# SEG_pressure_gauge_up_V2_1.net
KiCad netlist of a schematic drawn in Altium Designer
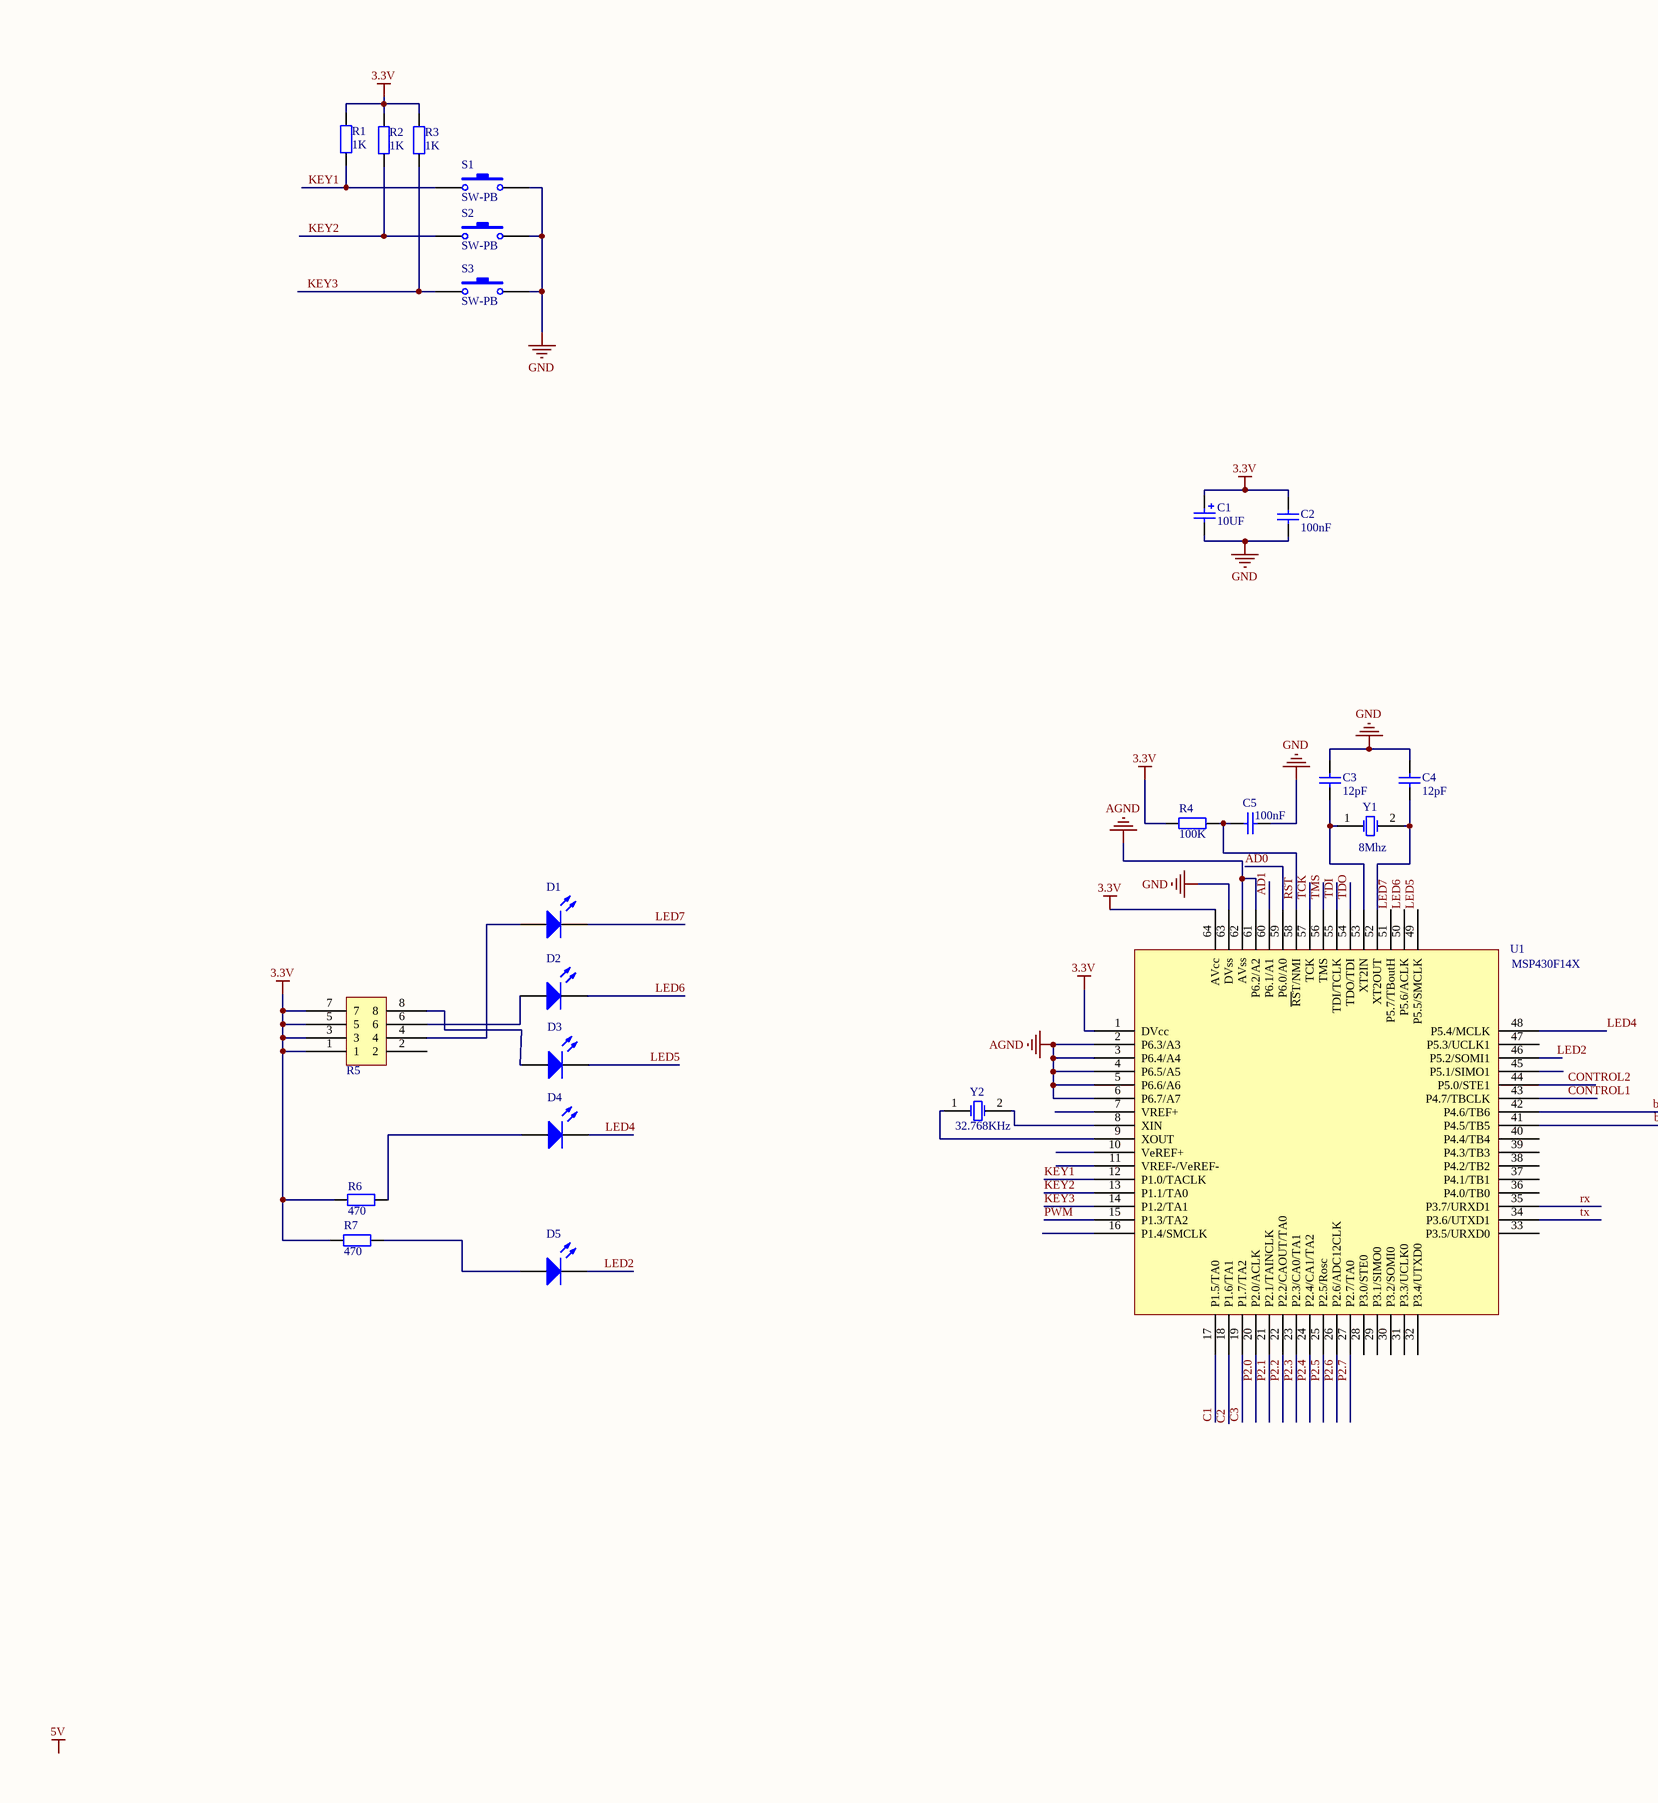
[diagram p0: SEG_pressure gauge_up  V2.1.SchDoc, left]
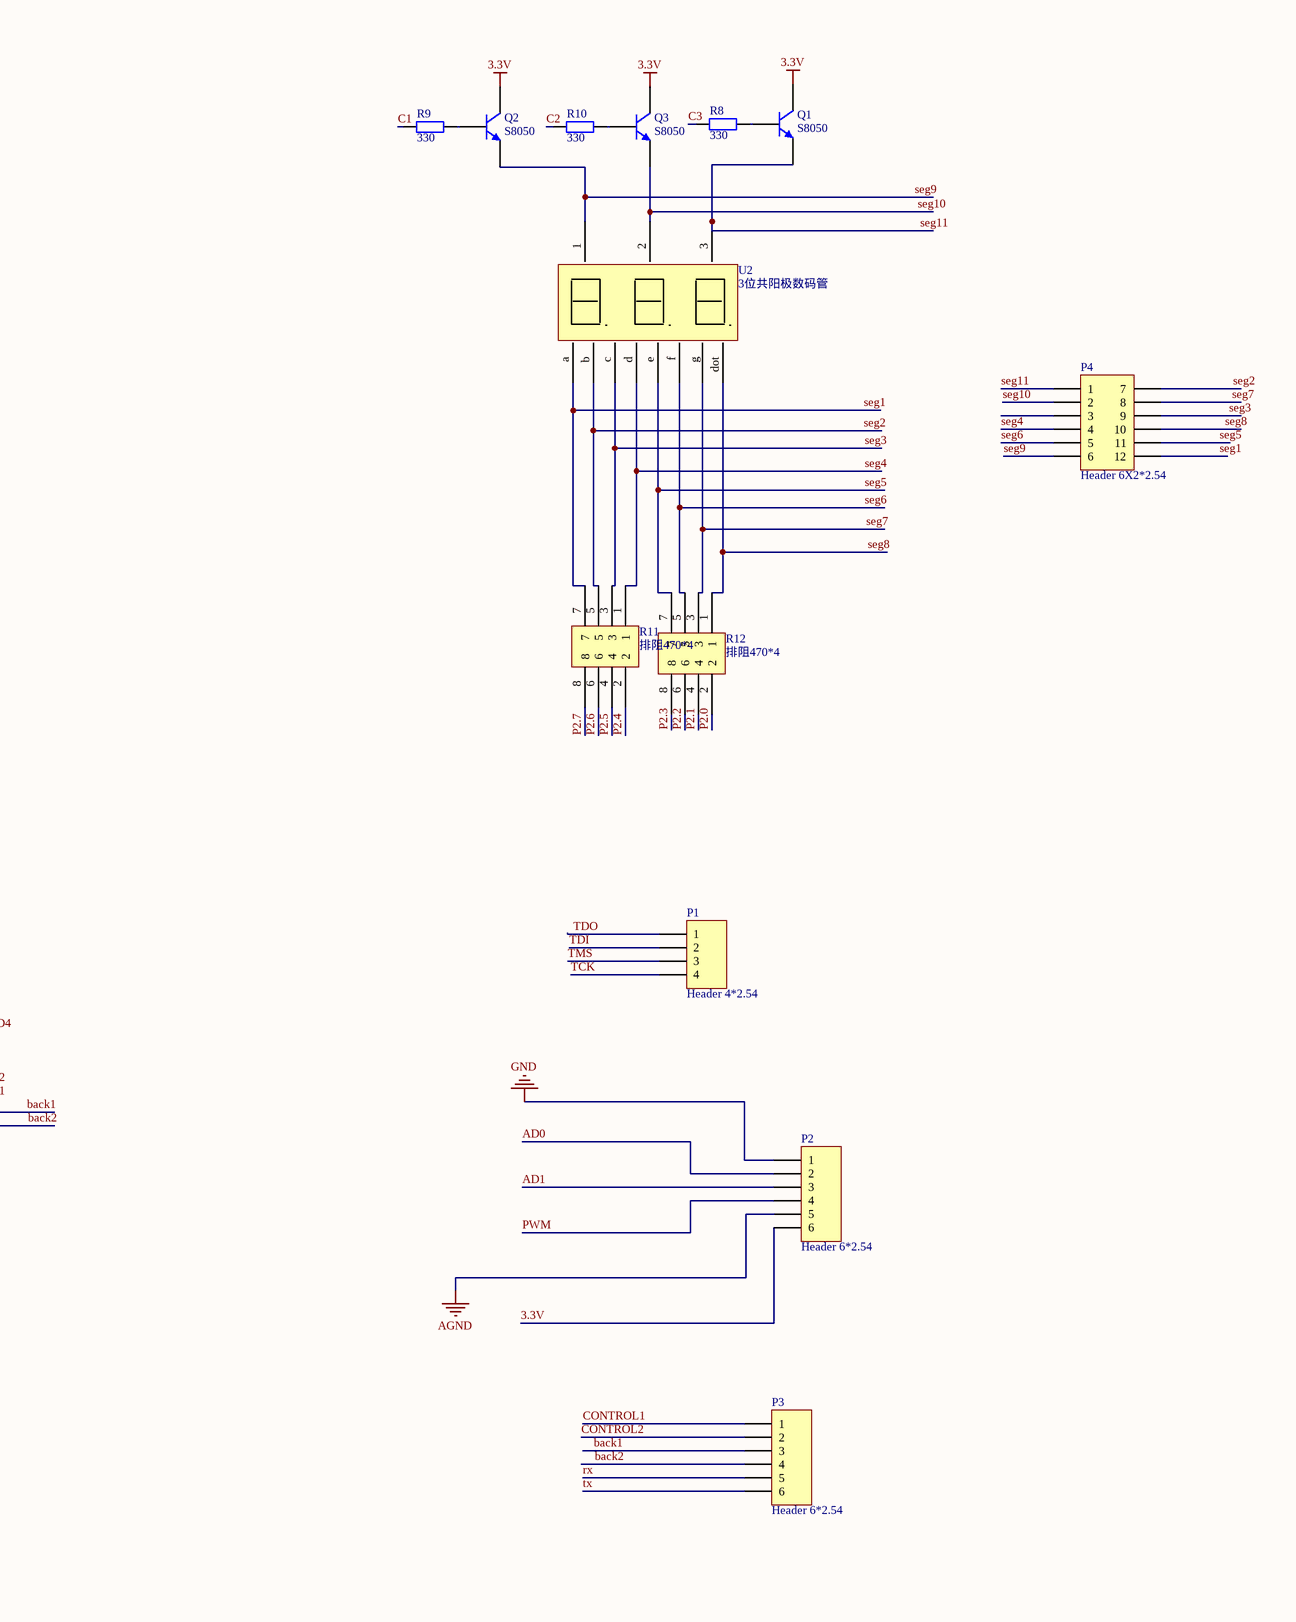
[diagram p1: SEG_pressure gauge_up  V2.1.SchDoc, right]

(export (version "E")
  (design (tool "Eeschema 10.0.6"))
  (components
    (comp (ref "C1")
      (value "10UF")
      (footprint "3216")
      (description "Polarized Capacitor (Axial)")
      (fields (field (name "Comment") "10uf") (field (name "PUBLISHER") "Altium Limited"))
      (libsource (lib "Miscellaneous Devices") (part "Cap Pol2"))
    )
    (comp (ref "C2")
      (value "100nF")
      (footprint "0805_C_Y")
      (description "Capacitor")
      (fields (field (name "Comment") "100nf") (field (name "PUBLISHER") "Altium Limited"))
      (libsource (lib "Miscellaneous Devices") (part "Cap"))
    )
    (comp (ref "C3")
      (value "12pF")
      (footprint "0805_C_Y")
      (description "Capacitor")
      (fields (field (name "Comment") "12pf") (field (name "PUBLISHER") "Altium Limited"))
      (libsource (lib "Miscellaneous Devices") (part "Cap"))
    )
    (comp (ref "C4")
      (value "12pF")
      (footprint "0805_C_Y")
      (description "Capacitor")
      (fields (field (name "Comment") "12pf") (field (name "PUBLISHER") "Altium Limited"))
      (libsource (lib "Miscellaneous Devices") (part "Cap"))
    )
    (comp (ref "C5")
      (value "100nF")
      (footprint "0805_C_Y")
      (description "Capacitor")
      (fields (field (name "Comment") "100nf") (field (name "PUBLISHER") "Altium Limited"))
      (libsource (lib "Miscellaneous Devices") (part "Cap"))
    )
    (comp (ref "D1")
      (value "LED")
      (footprint "LED")
      (description "Typical INFRARED GaAs LED")
      (fields (field (name "PUBLISHER") "Altium Limited"))
      (libsource (lib "Miscellaneous Devices") (part "LED0"))
    )
    (comp (ref "D2")
      (value "LED")
      (footprint "LED")
      (description "Typical INFRARED GaAs LED")
      (fields (field (name "PUBLISHER") "Altium Limited"))
      (libsource (lib "Miscellaneous Devices") (part "LED0"))
    )
    (comp (ref "D3")
      (value "LED")
      (footprint "LED")
      (description "Typical INFRARED GaAs LED")
      (fields (field (name "PUBLISHER") "Altium Limited"))
      (libsource (lib "Miscellaneous Devices") (part "LED0"))
    )
    (comp (ref "D4")
      (value "LED")
      (footprint "LED")
      (description "Typical INFRARED GaAs LED")
      (fields (field (name "PUBLISHER") "Altium Limited"))
      (libsource (lib "Miscellaneous Devices") (part "LED0"))
    )
    (comp (ref "D5")
      (value "LED")
      (footprint "LED")
      (description "Typical INFRARED GaAs LED")
      (fields (field (name "PUBLISHER") "Altium Limited"))
      (libsource (lib "Miscellaneous Devices") (part "LED0"))
    )
    (comp (ref "P1")
      (value "Header 4*2.54")
      (footprint "HDR1X4")
      (description "Header, 4-Pin")
      (fields (field (name "PUBLISHER") "Altium Limited"))
      (libsource (lib "Miscellaneous Connectors") (part "Header 4"))
    )
    (comp (ref "P2")
      (value "Header 6*2.54")
      (footprint "SEG_pressure gauge_up  V2.1:HDR1X6")
      (description "Header, 6-Pin")
      (fields (field (name "PUBLISHER") "Altium Limited"))
      (libsource (lib "Miscellaneous Connectors") (part "Header 6"))
    )
    (comp (ref "P3")
      (value "Header 6*2.54")
      (footprint "SEG_pressure gauge_up  V2.1:HDR1X6")
      (description "Header, 6-Pin")
      (fields (field (name "PUBLISHER") "Altium Limited"))
      (libsource (lib "Miscellaneous Connectors") (part "Header 6"))
    )
    (comp (ref "P4")
      (value "Header 6X2*2.54")
      (footprint "HDR2X6_CEN")
      (description "Header, 6-Pin, Dual row")
      (fields (field (name "PUBLISHER") "Altium Limited"))
      (libsource (lib "Miscellaneous Connectors") (part "Header 6X2A"))
    )
    (comp (ref "Q1")
      (value "S8050")
      (footprint "SOT-23_Y")
      (description "NPN General Purpose Amplifier")
      (fields (field (name "PUBLISHER") "Altium Limited"))
      (libsource (lib "Miscellaneous Devices") (part "2N3904"))
    )
    (comp (ref "Q2")
      (value "S8050")
      (footprint "SOT-23_Y")
      (description "NPN General Purpose Amplifier")
      (fields (field (name "PUBLISHER") "Altium Limited"))
      (libsource (lib "Miscellaneous Devices") (part "2N3904"))
    )
    (comp (ref "Q3")
      (value "S8050")
      (footprint "SOT-23_Y")
      (description "NPN General Purpose Amplifier")
      (fields (field (name "PUBLISHER") "Altium Limited"))
      (libsource (lib "Miscellaneous Devices") (part "2N3904"))
    )
    (comp (ref "R1")
      (value "1K")
      (footprint "0805_R_Y")
      (description "Resistor")
      (fields (field (name "Comment") "1k") (field (name "PUBLISHER") "Altium Limited"))
      (libsource (lib "") (part "Res2_1"))
    )
    (comp (ref "R2")
      (value "1K")
      (footprint "0805_R_Y")
      (description "Resistor")
      (fields (field (name "Comment") "1k") (field (name "PUBLISHER") "Altium Limited"))
      (libsource (lib "") (part "Res2_1"))
    )
    (comp (ref "R3")
      (value "1K")
      (footprint "0805_R_Y")
      (description "Resistor")
      (fields (field (name "Comment") "1k") (field (name "PUBLISHER") "Altium Limited"))
      (libsource (lib "") (part "Res2_1"))
    )
    (comp (ref "R4")
      (value "100K")
      (footprint "0805_R_Y")
      (description "Resistor")
      (fields (field (name "Comment") "100k") (field (name "PUBLISHER") "Altium Limited"))
      (libsource (lib "Miscellaneous Devices") (part "Res2"))
    )
    (comp (ref "R5") (value "排阻470*4") (footprint "8P4R_0603") (libsource (lib "biao2") (part "排阻 8P4R")))
    (comp (ref "R6")
      (value "470")
      (footprint "0805_R_Y")
      (description "Resistor")
      (fields (field (name "PUBLISHER") "Altium Limited"))
      (libsource (lib "Miscellaneous Devices") (part "Res2"))
    )
    (comp (ref "R7")
      (value "470")
      (footprint "0805_R_Y")
      (description "Resistor")
      (fields (field (name "PUBLISHER") "Altium Limited"))
      (libsource (lib "Miscellaneous Devices") (part "Res2"))
    )
    (comp (ref "R8")
      (value "330")
      (footprint "0805_R_Y")
      (description "Resistor")
      (fields (field (name "PUBLISHER") "Altium Limited"))
      (libsource (lib "") (part "Res2_2"))
    )
    (comp (ref "R9")
      (value "330")
      (footprint "0805_R_Y")
      (description "Resistor")
      (fields (field (name "PUBLISHER") "Altium Limited"))
      (libsource (lib "") (part "Res2_2"))
    )
    (comp (ref "R10")
      (value "330")
      (footprint "0805_R_Y")
      (description "Resistor")
      (fields (field (name "PUBLISHER") "Altium Limited"))
      (libsource (lib "") (part "Res2_2"))
    )
    (comp (ref "R11") (value "排阻470*4") (footprint "8P4R_0603") (libsource (lib "xianshi") (part "排阻 8P4R")))
    (comp (ref "R12") (value "排阻470*4") (footprint "8P4R_0603") (libsource (lib "xianshi") (part "排阻 8P4R")))
    (comp (ref "S1")
      (value "SW-PB")
      (footprint "SW-SMD1")
      (description "Switch")
      (fields (field (name "PUBLISHER") "Altium Limited"))
      (libsource (lib "Miscellaneous Devices") (part "SW-PB"))
    )
    (comp (ref "S2")
      (value "SW-PB")
      (footprint "SW-SMD1")
      (description "Switch")
      (fields (field (name "PUBLISHER") "Altium Limited"))
      (libsource (lib "Miscellaneous Devices") (part "SW-PB"))
    )
    (comp (ref "S3")
      (value "SW-PB")
      (footprint "SW-SMD1")
      (description "Switch")
      (fields (field (name "PUBLISHER") "Altium Limited"))
      (libsource (lib "Miscellaneous Devices") (part "SW-PB"))
    )
    (comp (ref "U1")
      (value "MSP430F14X")
      (footprint "S-PQFP-G64_Y")
      (libsource (lib "MSP430原理图") (part "MSP430F14X"))
    )
    (comp (ref "U2")
      (value "3位共阳极数码管")
      (footprint "xianshi:3位数码管0.56")
      (libsource (lib "kelei") (part "3位共阳极数码管"))
    )
    (comp (ref "Y1")
      (value "8Mhz")
      (footprint "HC-49/S_Y")
      (description "Crystal Oscillator")
      (fields (field (name "Comment") "晶振8M") (field (name "PUBLISHER") "Altium Limited"))
      (libsource (lib "Miscellaneous Devices") (part "XTAL"))
    )
    (comp (ref "Y2")
      (value "32.768KHz")
      (footprint "Crastal_32.768_Y")
      (description "Crystal Oscillator")
      (fields (field (name "Comment") "晶振32.768k") (field (name "PUBLISHER") "Altium Limited"))
      (libsource (lib "Miscellaneous Devices") (part "XTAL"))
    )
  )
  (nets
    (net (code "1") (name "/AD0") (class "Default")
      (node (ref "P2") (pin "2") (pinfunction "2_2") (pintype "passive"))
      (node (ref "U1") (pin "59") (pinfunction "P6.0/A0_59") (pintype "power_in"))
    )
    (net (code "2") (name "/AD1") (class "Default")
      (node (ref "P2") (pin "3") (pinfunction "3_3") (pintype "passive"))
      (node (ref "U1") (pin "60") (pinfunction "P6.1/A1_60") (pintype "power_in"))
    )
    (net (code "3") (name "/C1") (class "Default")
      (node (ref "R9") (pin "2") (pinfunction "2_2") (pintype "passive"))
      (node (ref "U1") (pin "17") (pinfunction "P1.5/TA0_17") (pintype "power_in"))
    )
    (net (code "4") (name "/C2") (class "Default")
      (node (ref "R10") (pin "2") (pinfunction "2_2") (pintype "passive"))
      (node (ref "U1") (pin "18") (pinfunction "P1.6/TA1_18") (pintype "power_in"))
    )
    (net (code "5") (name "/C3") (class "Default")
      (node (ref "R8") (pin "2") (pinfunction "2_2") (pintype "passive"))
      (node (ref "U1") (pin "19") (pinfunction "P1.7/TA2_19") (pintype "power_in"))
    )
    (net (code "6") (name "/CONTROL1") (class "Default")
      (node (ref "P3") (pin "1") (pinfunction "1_1") (pintype "passive"))
      (node (ref "U1") (pin "43") (pinfunction "P4.7/TBCLK_43") (pintype "power_in"))
    )
    (net (code "7") (name "/CONTROL2") (class "Default")
      (node (ref "P3") (pin "2") (pinfunction "2_2") (pintype "passive"))
      (node (ref "U1") (pin "44") (pinfunction "P5.0/STE1_44") (pintype "power_in"))
    )
    (net (code "8") (name "/KEY1") (class "Default")
      (node (ref "R1") (pin "1") (pinfunction "1_1") (pintype "passive"))
      (node (ref "S1") (pin "1") (pinfunction "1_1") (pintype "passive"))
      (node (ref "U1") (pin "12") (pinfunction "P1.0/TACLK_12") (pintype "power_in"))
    )
    (net (code "9") (name "/KEY2") (class "Default")
      (node (ref "R2") (pin "1") (pinfunction "1_1") (pintype "passive"))
      (node (ref "S2") (pin "1") (pinfunction "1_1") (pintype "passive"))
      (node (ref "U1") (pin "13") (pinfunction "P1.1/TA0_13") (pintype "power_in"))
    )
    (net (code "10") (name "/KEY3") (class "Default")
      (node (ref "R3") (pin "1") (pinfunction "1_1") (pintype "passive"))
      (node (ref "S3") (pin "1") (pinfunction "1_1") (pintype "passive"))
      (node (ref "U1") (pin "14") (pinfunction "P1.2/TA1_14") (pintype "power_in"))
    )
    (net (code "11") (name "/LED2") (class "Default")
      (node (ref "D5") (pin "2") (pinfunction "K_2") (pintype "passive"))
      (node (ref "U1") (pin "46") (pinfunction "P5.2/SOMI1_46") (pintype "power_in"))
    )
    (net (code "12") (name "/LED4") (class "Default")
      (node (ref "D4") (pin "2") (pinfunction "K_2") (pintype "passive"))
      (node (ref "U1") (pin "48") (pinfunction "P5.4/MCLK_48") (pintype "power_in"))
    )
    (net (code "13") (name "/LED5") (class "Default")
      (node (ref "D3") (pin "2") (pinfunction "K_2") (pintype "passive"))
      (node (ref "U1") (pin "49") (pinfunction "P5.5/SMCLK_49") (pintype "power_in"))
    )
    (net (code "14") (name "/LED6") (class "Default")
      (node (ref "D2") (pin "2") (pinfunction "K_2") (pintype "passive"))
      (node (ref "U1") (pin "50") (pinfunction "P5.6/ACLK_50") (pintype "power_in"))
    )
    (net (code "15") (name "/LED7") (class "Default")
      (node (ref "D1") (pin "2") (pinfunction "K_2") (pintype "passive"))
      (node (ref "U1") (pin "51") (pinfunction "P5.7/TBoutH_51") (pintype "power_in"))
    )
    (net (code "16") (name "/P2.0") (class "Default")
      (node (ref "R12") (pin "2") (pinfunction "2_2") (pintype "passive"))
      (node (ref "U1") (pin "20") (pinfunction "P2.0/ACLK_20") (pintype "power_in"))
    )
    (net (code "17") (name "/P2.1") (class "Default")
      (node (ref "R12") (pin "4") (pinfunction "4_4") (pintype "passive"))
      (node (ref "U1") (pin "21") (pinfunction "P2.1/TAINCLK_21") (pintype "power_in"))
    )
    (net (code "18") (name "/P2.2") (class "Default")
      (node (ref "R12") (pin "6") (pinfunction "6_6") (pintype "passive"))
      (node (ref "U1") (pin "22") (pinfunction "P2.2/CAOUT/TA0_22") (pintype "power_in"))
    )
    (net (code "19") (name "/P2.3") (class "Default")
      (node (ref "R12") (pin "8") (pinfunction "8_8") (pintype "passive"))
      (node (ref "U1") (pin "23") (pinfunction "P2.3/CA0/TA1_23") (pintype "power_in"))
    )
    (net (code "20") (name "/P2.4") (class "Default")
      (node (ref "R11") (pin "2") (pinfunction "2_2") (pintype "passive"))
      (node (ref "U1") (pin "24") (pinfunction "P2.4/CA1/TA2_24") (pintype "power_in"))
    )
    (net (code "21") (name "/P2.5") (class "Default")
      (node (ref "R11") (pin "4") (pinfunction "4_4") (pintype "passive"))
      (node (ref "U1") (pin "25") (pinfunction "P2.5/Rosc_25") (pintype "power_in"))
    )
    (net (code "22") (name "/P2.6") (class "Default")
      (node (ref "R11") (pin "6") (pinfunction "6_6") (pintype "passive"))
      (node (ref "U1") (pin "26") (pinfunction "P2.6/ADC12CLK_26") (pintype "power_in"))
    )
    (net (code "23") (name "/P2.7") (class "Default")
      (node (ref "R11") (pin "8") (pinfunction "8_8") (pintype "passive"))
      (node (ref "U1") (pin "27") (pinfunction "P2.7/TA0_27") (pintype "power_in"))
    )
    (net (code "24") (name "/PWM") (class "Default")
      (node (ref "P2") (pin "4") (pinfunction "4_4") (pintype "passive"))
      (node (ref "U1") (pin "15") (pinfunction "P1.3/TA2_15") (pintype "power_in"))
    )
    (net (code "25") (name "/RST") (class "Default")
      (node (ref "C5") (pin "2") (pinfunction "2_2") (pintype "passive"))
      (node (ref "R4") (pin "2") (pinfunction "2_2") (pintype "passive"))
      (node (ref "U1") (pin "58") (pinfunction "~{RS}T/NMI_58") (pintype "power_in"))
    )
    (net (code "26") (name "/TCK") (class "Default")
      (node (ref "P1") (pin "4") (pinfunction "4_4") (pintype "passive"))
      (node (ref "U1") (pin "57") (pinfunction "TCK_57") (pintype "power_in"))
    )
    (net (code "27") (name "/TDI") (class "Default")
      (node (ref "P1") (pin "2") (pinfunction "2_2") (pintype "passive"))
      (node (ref "U1") (pin "55") (pinfunction "TDI/TCLK_55") (pintype "power_in"))
    )
    (net (code "28") (name "/TDO") (class "Default")
      (node (ref "P1") (pin "1") (pinfunction "1_1") (pintype "passive"))
      (node (ref "U1") (pin "54") (pinfunction "TDO/TDI_54") (pintype "power_in"))
    )
    (net (code "29") (name "/TMS") (class "Default")
      (node (ref "P1") (pin "3") (pinfunction "3_3") (pintype "passive"))
      (node (ref "U1") (pin "56") (pinfunction "TMS_56") (pintype "power_in"))
    )
    (net (code "30") (name "/back1") (class "Default")
      (node (ref "P3") (pin "3") (pinfunction "3_3") (pintype "passive"))
      (node (ref "U1") (pin "42") (pinfunction "P4.6/TB6_42") (pintype "power_in"))
    )
    (net (code "31") (name "/back2") (class "Default")
      (node (ref "P3") (pin "4") (pinfunction "4_4") (pintype "passive"))
      (node (ref "U1") (pin "41") (pinfunction "P4.5/TB5_41") (pintype "power_in"))
    )
    (net (code "32") (name "/rx") (class "Default")
      (node (ref "P3") (pin "5") (pinfunction "5_5") (pintype "passive"))
      (node (ref "U1") (pin "35") (pinfunction "P3.7/URXD1_35") (pintype "power_in"))
    )
    (net (code "33") (name "/seg1") (class "Default")
      (node (ref "P4") (pin "12") (pinfunction "12_12") (pintype "passive"))
      (node (ref "R11") (pin "7") (pinfunction "7_7") (pintype "passive"))
      (node (ref "U2") (pin "a") (pinfunction "a_a") (pintype "passive"))
    )
    (net (code "34") (name "/seg2") (class "Default")
      (node (ref "P4") (pin "7") (pinfunction "7_7") (pintype "passive"))
      (node (ref "R11") (pin "5") (pinfunction "5_5") (pintype "passive"))
      (node (ref "U2") (pin "b") (pinfunction "b_b") (pintype "passive"))
    )
    (net (code "35") (name "/seg3") (class "Default")
      (node (ref "P4") (pin "9") (pinfunction "9_9") (pintype "passive"))
      (node (ref "R11") (pin "3") (pinfunction "3_3") (pintype "passive"))
      (node (ref "U2") (pin "c") (pinfunction "c_c") (pintype "passive"))
    )
    (net (code "36") (name "/seg4") (class "Default")
      (node (ref "P4") (pin "4") (pinfunction "4_4") (pintype "passive"))
      (node (ref "R11") (pin "1") (pinfunction "1_1") (pintype "passive"))
      (node (ref "U2") (pin "d") (pinfunction "d_d") (pintype "passive"))
    )
    (net (code "37") (name "/seg5") (class "Default")
      (node (ref "P4") (pin "11") (pinfunction "11_11") (pintype "passive"))
      (node (ref "R12") (pin "7") (pinfunction "7_7") (pintype "passive"))
      (node (ref "U2") (pin "e") (pinfunction "e_e") (pintype "passive"))
    )
    (net (code "38") (name "/seg6") (class "Default")
      (node (ref "P4") (pin "5") (pinfunction "5_5") (pintype "passive"))
      (node (ref "R12") (pin "5") (pinfunction "5_5") (pintype "passive"))
      (node (ref "U2") (pin "f") (pinfunction "f_f") (pintype "passive"))
    )
    (net (code "39") (name "/seg7") (class "Default")
      (node (ref "P4") (pin "8") (pinfunction "8_8") (pintype "passive"))
      (node (ref "R12") (pin "3") (pinfunction "3_3") (pintype "passive"))
      (node (ref "U2") (pin "g") (pinfunction "g_g") (pintype "passive"))
    )
    (net (code "40") (name "/seg8") (class "Default")
      (node (ref "P4") (pin "10") (pinfunction "10_10") (pintype "passive"))
      (node (ref "R12") (pin "1") (pinfunction "1_1") (pintype "passive"))
      (node (ref "U2") (pin "dot") (pinfunction "dot_dot") (pintype "passive"))
    )
    (net (code "41") (name "/seg9") (class "Default")
      (node (ref "P4") (pin "6") (pinfunction "6_6") (pintype "passive"))
      (node (ref "Q2") (pin "2") (pinfunction "E_2") (pintype "passive"))
      (node (ref "U2") (pin "1") (pinfunction "1_1") (pintype "passive"))
    )
    (net (code "42") (name "/seg10") (class "Default")
      (node (ref "P4") (pin "2") (pinfunction "2_2") (pintype "passive"))
      (node (ref "Q3") (pin "2") (pinfunction "E_2") (pintype "passive"))
      (node (ref "U2") (pin "2") (pinfunction "2_2") (pintype "passive"))
    )
    (net (code "43") (name "/seg11") (class "Default")
      (node (ref "P4") (pin "1") (pinfunction "1_1") (pintype "passive"))
      (node (ref "Q1") (pin "2") (pinfunction "E_2") (pintype "passive"))
      (node (ref "U2") (pin "3") (pinfunction "3_3") (pintype "passive"))
    )
    (net (code "44") (name "/tx") (class "Default")
      (node (ref "P3") (pin "6") (pinfunction "6_6") (pintype "passive"))
      (node (ref "U1") (pin "34") (pinfunction "P3.6/UTXD1_34") (pintype "power_in"))
    )
    (net (code "45") (name "3.3V") (class "Default")
      (node (ref "C1") (pin "1") (pinfunction "1_1") (pintype "passive"))
      (node (ref "C2") (pin "1") (pinfunction "1_1") (pintype "passive"))
      (node (ref "P2") (pin "6") (pinfunction "6_6") (pintype "passive"))
      (node (ref "Q1") (pin "3") (pinfunction "C_3") (pintype "passive"))
      (node (ref "Q2") (pin "3") (pinfunction "C_3") (pintype "passive"))
      (node (ref "Q3") (pin "3") (pinfunction "C_3") (pintype "passive"))
      (node (ref "R1") (pin "2") (pinfunction "2_2") (pintype "passive"))
      (node (ref "R2") (pin "2") (pinfunction "2_2") (pintype "passive"))
      (node (ref "R3") (pin "2") (pinfunction "2_2") (pintype "passive"))
      (node (ref "R4") (pin "1") (pinfunction "1_1") (pintype "passive"))
      (node (ref "R5") (pin "1") (pinfunction "1_1") (pintype "passive"))
      (node (ref "R5") (pin "3") (pinfunction "3_3") (pintype "passive"))
      (node (ref "R5") (pin "5") (pinfunction "5_5") (pintype "passive"))
      (node (ref "R5") (pin "7") (pinfunction "7_7") (pintype "passive"))
      (node (ref "R6") (pin "1") (pinfunction "1_1") (pintype "passive"))
      (node (ref "R7") (pin "1") (pinfunction "1_1") (pintype "passive"))
      (node (ref "U1") (pin "1") (pinfunction "DVcc_1") (pintype "power_in"))
      (node (ref "U1") (pin "64") (pinfunction "AVcc_64") (pintype "power_in"))
    )
    (net (code "47") (name "AGND") (class "Default")
      (node (ref "P2") (pin "5") (pinfunction "5_5") (pintype "passive"))
      (node (ref "U1") (pin "2") (pinfunction "P6.3/A3_2") (pintype "power_in"))
      (node (ref "U1") (pin "3") (pinfunction "P6.4/A4_3") (pintype "power_in"))
      (node (ref "U1") (pin "4") (pinfunction "P6.5/A5_4") (pintype "power_in"))
      (node (ref "U1") (pin "5") (pinfunction "P6.6/A6_5") (pintype "power_in"))
      (node (ref "U1") (pin "6") (pinfunction "P6.7/A7_6") (pintype "power_in"))
      (node (ref "U1") (pin "61") (pinfunction "P6.2/A2_61") (pintype "power_in"))
      (node (ref "U1") (pin "62") (pinfunction "AVss_62") (pintype "power_in"))
    )
    (net (code "48") (name "GND") (class "Default")
      (node (ref "C1") (pin "2") (pinfunction "2_2") (pintype "passive"))
      (node (ref "C2") (pin "2") (pinfunction "2_2") (pintype "passive"))
      (node (ref "C3") (pin "1") (pinfunction "1_1") (pintype "passive"))
      (node (ref "C4") (pin "1") (pinfunction "1_1") (pintype "passive"))
      (node (ref "C5") (pin "1") (pinfunction "1_1") (pintype "passive"))
      (node (ref "P2") (pin "1") (pinfunction "1_1") (pintype "passive"))
      (node (ref "S1") (pin "2") (pinfunction "2_2") (pintype "passive"))
      (node (ref "S2") (pin "2") (pinfunction "2_2") (pintype "passive"))
      (node (ref "S3") (pin "2") (pinfunction "2_2") (pintype "passive"))
      (node (ref "U1") (pin "63") (pinfunction "DVss_63") (pintype "power_in"))
    )
    (net (code "49") (name "Net-(D1-A)") (class "Default")
      (node (ref "D1") (pin "1") (pinfunction "A_1") (pintype "passive"))
      (node (ref "R5") (pin "4") (pinfunction "4_4") (pintype "passive"))
    )
    (net (code "50") (name "Net-(D2-A)") (class "Default")
      (node (ref "D2") (pin "1") (pinfunction "A_1") (pintype "passive"))
      (node (ref "R5") (pin "6") (pinfunction "6_6") (pintype "passive"))
    )
    (net (code "51") (name "Net-(D3-A)") (class "Default")
      (node (ref "D3") (pin "1") (pinfunction "A_1") (pintype "passive"))
      (node (ref "R5") (pin "8") (pinfunction "8_8") (pintype "passive"))
    )
    (net (code "52") (name "Net-(D4-A)") (class "Default")
      (node (ref "D4") (pin "1") (pinfunction "A_1") (pintype "passive"))
      (node (ref "R6") (pin "2") (pinfunction "2_2") (pintype "passive"))
    )
    (net (code "53") (name "Net-(D5-A)") (class "Default")
      (node (ref "D5") (pin "1") (pinfunction "A_1") (pintype "passive"))
      (node (ref "R7") (pin "2") (pinfunction "2_2") (pintype "passive"))
    )
    (net (code "54") (name "Net-(Q1-B)") (class "Default")
      (node (ref "Q1") (pin "1") (pinfunction "B_1") (pintype "passive"))
      (node (ref "R8") (pin "1") (pinfunction "1_1") (pintype "passive"))
    )
    (net (code "55") (name "Net-(Q2-B)") (class "Default")
      (node (ref "Q2") (pin "1") (pinfunction "B_1") (pintype "passive"))
      (node (ref "R9") (pin "1") (pinfunction "1_1") (pintype "passive"))
    )
    (net (code "56") (name "Net-(Q3-B)") (class "Default")
      (node (ref "Q3") (pin "1") (pinfunction "B_1") (pintype "passive"))
      (node (ref "R10") (pin "1") (pinfunction "1_1") (pintype "passive"))
    )
    (net (code "57") (name "Net-(U1-XIN)") (class "Default")
      (node (ref "U1") (pin "8") (pinfunction "XIN_8") (pintype "power_in"))
      (node (ref "Y2") (pin "2") (pinfunction "OSC2_2") (pintype "passive"))
    )
    (net (code "58") (name "Net-(U1-XOUT)") (class "Default")
      (node (ref "U1") (pin "9") (pinfunction "XOUT_9") (pintype "power_in"))
      (node (ref "Y2") (pin "1") (pinfunction "OSC1_1") (pintype "passive"))
    )
    (net (code "59") (name "Net-(U1-XT2IN)") (class "Default")
      (node (ref "C3") (pin "2") (pinfunction "2_2") (pintype "passive"))
      (node (ref "U1") (pin "53") (pinfunction "XT2IN_53") (pintype "power_in"))
      (node (ref "Y1") (pin "1") (pinfunction "OSC1_1") (pintype "passive"))
    )
    (net (code "60") (name "Net-(U1-XT2OUT)") (class "Default")
      (node (ref "C4") (pin "2") (pinfunction "2_2") (pintype "passive"))
      (node (ref "U1") (pin "52") (pinfunction "XT2OUT_52") (pintype "power_in"))
      (node (ref "Y1") (pin "2") (pinfunction "OSC2_2") (pintype "passive"))
    )
    (net (code "61") (name "unconnected-(P4-Pad3)") (class "Default")
      (node (ref "P4") (pin "3") (pinfunction "3_3") (pintype "passive"))
    )
    (net (code "62") (name "unconnected-(R5-Pad2)") (class "Default")
      (node (ref "R5") (pin "2") (pinfunction "2_2") (pintype "passive"))
    )
    (net (code "63") (name "unconnected-(U1-P1.4{slash}SMCLK-Pad16)") (class "Default")
      (node (ref "U1") (pin "16") (pinfunction "P1.4/SMCLK_16") (pintype "power_in"))
    )
    (net (code "64") (name "unconnected-(U1-P3.0{slash}STE0-Pad28)") (class "Default")
      (node (ref "U1") (pin "28") (pinfunction "P3.0/STE0_28") (pintype "power_in"))
    )
    (net (code "65") (name "unconnected-(U1-P3.1{slash}SIMO0-Pad29)") (class "Default")
      (node (ref "U1") (pin "29") (pinfunction "P3.1/SIMO0_29") (pintype "power_in"))
    )
    (net (code "66") (name "unconnected-(U1-P3.2{slash}SOMI0-Pad30)") (class "Default")
      (node (ref "U1") (pin "30") (pinfunction "P3.2/SOMI0_30") (pintype "power_in"))
    )
    (net (code "67") (name "unconnected-(U1-P3.3{slash}UCLK0-Pad31)") (class "Default")
      (node (ref "U1") (pin "31") (pinfunction "P3.3/UCLK0_31") (pintype "power_in"))
    )
    (net (code "68") (name "unconnected-(U1-P3.4{slash}UTXD0-Pad32)") (class "Default")
      (node (ref "U1") (pin "32") (pinfunction "P3.4/UTXD0_32") (pintype "power_in"))
    )
    (net (code "69") (name "unconnected-(U1-P3.5{slash}URXD0-Pad33)") (class "Default")
      (node (ref "U1") (pin "33") (pinfunction "P3.5/URXD0_33") (pintype "power_in"))
    )
    (net (code "70") (name "unconnected-(U1-P4.0{slash}TB0-Pad36)") (class "Default")
      (node (ref "U1") (pin "36") (pinfunction "P4.0/TB0_36") (pintype "power_in"))
    )
    (net (code "71") (name "unconnected-(U1-P4.1{slash}TB1-Pad37)") (class "Default")
      (node (ref "U1") (pin "37") (pinfunction "P4.1/TB1_37") (pintype "power_in"))
    )
    (net (code "72") (name "unconnected-(U1-P4.2{slash}TB2-Pad38)") (class "Default")
      (node (ref "U1") (pin "38") (pinfunction "P4.2/TB2_38") (pintype "power_in"))
    )
    (net (code "73") (name "unconnected-(U1-P4.3{slash}TB3-Pad39)") (class "Default")
      (node (ref "U1") (pin "39") (pinfunction "P4.3/TB3_39") (pintype "power_in"))
    )
    (net (code "74") (name "unconnected-(U1-P4.4{slash}TB4-Pad40)") (class "Default")
      (node (ref "U1") (pin "40") (pinfunction "P4.4/TB4_40") (pintype "power_in"))
    )
    (net (code "75") (name "unconnected-(U1-P5.1{slash}SIMO1-Pad45)") (class "Default")
      (node (ref "U1") (pin "45") (pinfunction "P5.1/SIMO1_45") (pintype "power_in"))
    )
    (net (code "76") (name "unconnected-(U1-P5.3{slash}UCLK1-Pad47)") (class "Default")
      (node (ref "U1") (pin "47") (pinfunction "P5.3/UCLK1_47") (pintype "power_in"))
    )
    (net (code "77") (name "unconnected-(U1-VREF+-Pad7)") (class "Default")
      (node (ref "U1") (pin "7") (pinfunction "VREF+_7") (pintype "power_in"))
    )
    (net (code "78") (name "unconnected-(U1-VREF-{slash}VeREF--Pad11)") (class "Default")
      (node (ref "U1") (pin "11") (pinfunction "VREF-/VeREF-_11") (pintype "power_in"))
    )
    (net (code "79") (name "unconnected-(U1-VeREF+-Pad10)") (class "Default")
      (node (ref "U1") (pin "10") (pinfunction "VeREF+_10") (pintype "power_in"))
    )
  )
)
